# JLink-OB-072-Wiki.net
KiCad netlist of a schematic drawn in Altium Designer
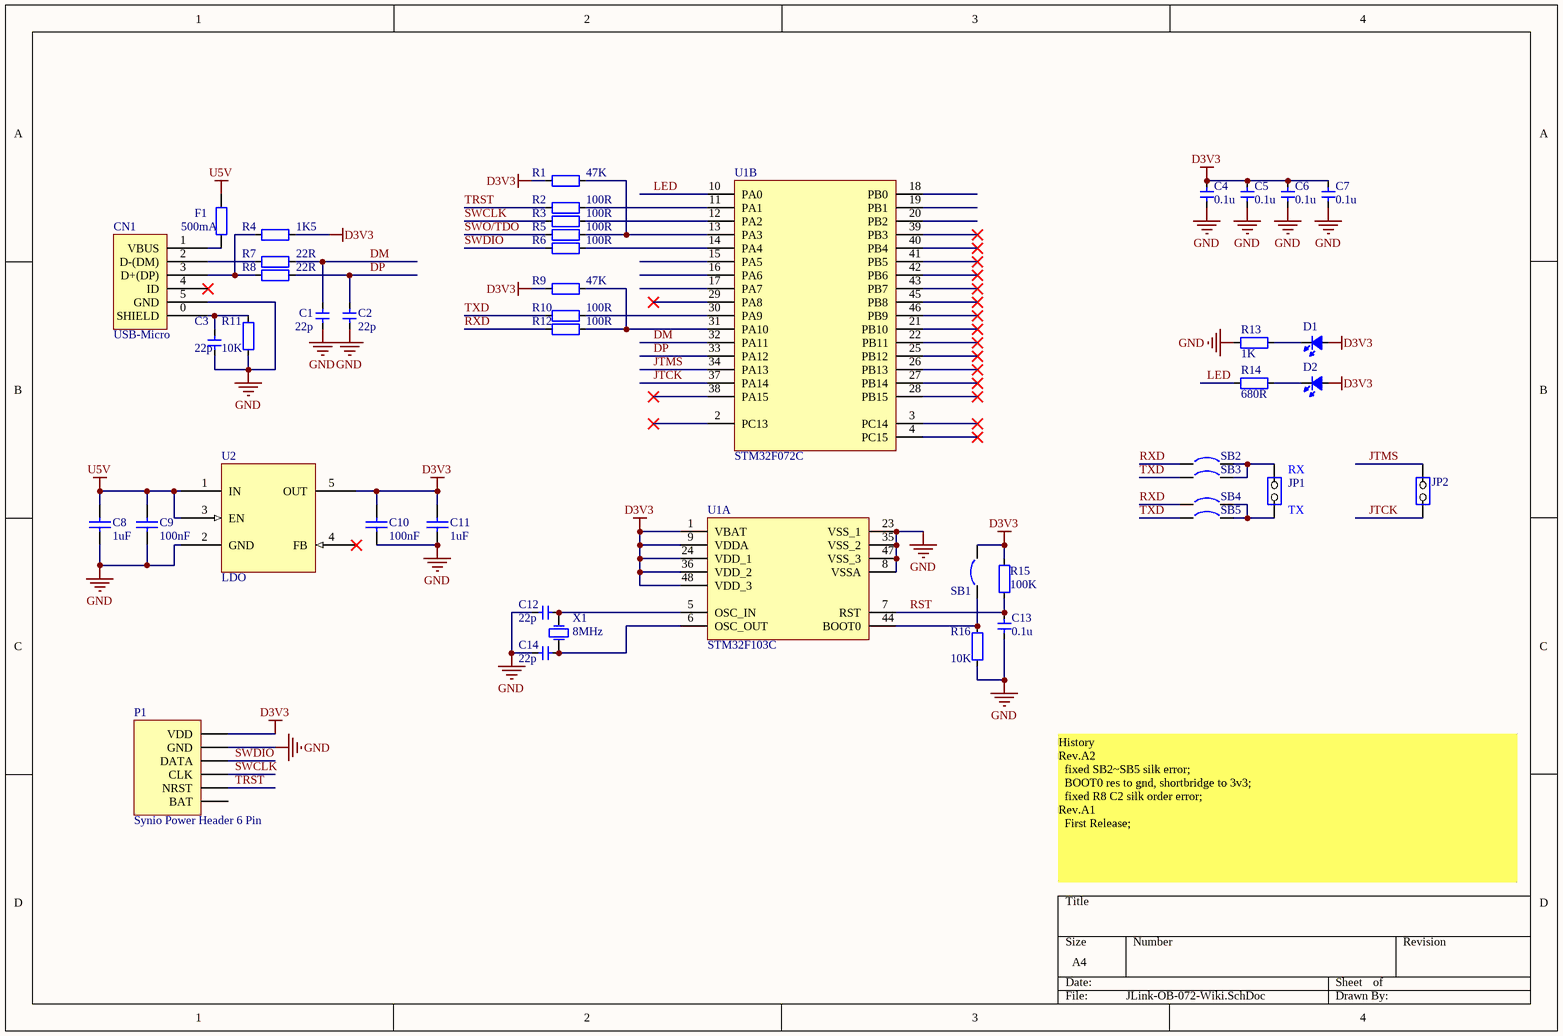
[diagram p0: JLink-OB-072-Wiki.SchDoc]

(export (version "E")
  (design (tool "Eeschema 10.0.6"))
  (components
    (comp (ref "C1")
      (value "22p")
      (footprint "0603C")
      (description "Capacitor")
      (fields (field (name "Comment") "Cap_0603"))
      (libsource (lib "altium-import") (part "root_1_Cap_0603_"))
    )
    (comp (ref "C2")
      (value "22p")
      (footprint "0603C")
      (description "Capacitor")
      (fields (field (name "Comment") "Cap_0603"))
      (libsource (lib "SCH_Passive") (part "Cap_0603"))
    )
    (comp (ref "C3")
      (value "22p")
      (footprint "0603C")
      (description "Capacitor")
      (fields (field (name "Comment") "Cap_0603"))
      (libsource (lib "SCH_Passive") (part "Cap_0603"))
    )
    (comp (ref "C4")
      (value "0.1u")
      (footprint "0603C")
      (description "Capacitor")
      (fields (field (name "Comment") "Cap_0603"))
      (libsource (lib "SCH_Passive") (part "Cap_0603"))
    )
    (comp (ref "C5")
      (value "0.1u")
      (footprint "0603C")
      (description "Capacitor")
      (fields (field (name "Comment") "Cap_0603"))
      (libsource (lib "SCH_Passive") (part "Cap_0603"))
    )
    (comp (ref "C6")
      (value "0.1u")
      (footprint "0603C")
      (description "Capacitor")
      (fields (field (name "Comment") "Cap_0603"))
      (libsource (lib "SCH_Passive") (part "Cap_0603"))
    )
    (comp (ref "C7")
      (value "0.1u")
      (footprint "0603C")
      (description "Capacitor")
      (fields (field (name "Comment") "Cap_0603"))
      (libsource (lib "SCH_Passive") (part "Cap_0603"))
    )
    (comp (ref "C8")
      (value "1uF")
      (footprint "0603C")
      (description "Capacitor 0402 / 0603 / 0805")
      (libsource (lib "MCD_TOOLS") (part "Capacitor_ST"))
    )
    (comp (ref "C9")
      (value "100nF")
      (footprint "0603C")
      (description "Capacitor 0402 / 0603 / 0805")
      (libsource (lib "MCD_TOOLS") (part "Capacitor_ST"))
    )
    (comp (ref "C10")
      (value "100nF")
      (footprint "0603C")
      (description "Capacitor 0402 / 0603 / 0805")
      (libsource (lib "MCD_TOOLS") (part "Capacitor_ST"))
    )
    (comp (ref "C11")
      (value "1uF")
      (footprint "0603C")
      (description "Capacitor 0402 / 0603 / 0805")
      (libsource (lib "MCD_TOOLS") (part "Capacitor_ST"))
    )
    (comp (ref "C12")
      (value "22p")
      (footprint "0603C")
      (description "Capacitor")
      (fields (field (name "Comment") "Cap_0603"))
      (libsource (lib "SCH_Passive") (part "Cap_0603"))
    )
    (comp (ref "C13")
      (value "0.1u")
      (footprint "0603C")
      (description "Capacitor")
      (fields (field (name "Comment") "Cap_0603"))
      (libsource (lib "SCH_Passive") (part "Cap_0603"))
    )
    (comp (ref "C14")
      (value "22p")
      (footprint "0603C")
      (description "Capacitor")
      (fields (field (name "Comment") "Cap_0603"))
      (libsource (lib "SCH_Passive") (part "Cap_0603"))
    )
    (comp (ref "CN1")
      (value "USB-Micro")
      (footprint "USB_MICRO_5S_B-2")
      (libsource (lib "USB") (part "USB-Micro"))
    )
    (comp (ref "D1")
      (value "LED_0603")
      (footprint "LED-0603")
      (description "LED")
      (libsource (lib "SCH_Active") (part "LED_0603"))
    )
    (comp (ref "D2")
      (value "LED_0603")
      (footprint "LED-0603")
      (description "LED")
      (libsource (lib "SCH_Active") (part "LED_0603"))
    )
    (comp (ref "F1")
      (value "500mA")
      (footprint "0805M")
      (description "Resistor")
      (fields (field (name "PUBLISHER") "Altium Limited"))
      (libsource (lib "Misc") (part "Res"))
    )
    (comp (ref "JP1") (value "JP2") (footprint "HDR1X2/2.54mm") (libsource (lib "Connector") (part "JP2")))
    (comp (ref "JP2") (value "JP2") (footprint "HDR1X2/2.54mm") (libsource (lib "Connector") (part "JP2")))
    (comp (ref "P1")
      (value "Synio Power Header 6 Pin")
      (footprint "HDR1X6/2.54MM")
      (libsource (lib "Connector") (part "Synio Power Header 6 Pin"))
    )
    (comp (ref "R1")
      (value "47K")
      (footprint "0603R")
      (description "Resistor")
      (fields (field (name "Comment") "Res_0603"))
      (libsource (lib "") (part "Res_0603_1"))
    )
    (comp (ref "R2")
      (value "100R")
      (footprint "0603R")
      (description "Resistor")
      (fields (field (name "Comment") "Res_0603"))
      (libsource (lib "altium-import") (part "root_0_Res_0603_"))
    )
    (comp (ref "R3")
      (value "100R")
      (footprint "0603R")
      (description "Resistor")
      (fields (field (name "Comment") "Res_0603"))
      (libsource (lib "SCH_Passive") (part "Res_0603"))
    )
    (comp (ref "R4")
      (value "1K5")
      (footprint "0603R")
      (description "Resistor")
      (fields (field (name "Comment") "Res_0603"))
      (libsource (lib "SCH_Passive") (part "Res_0603"))
    )
    (comp (ref "R5")
      (value "100R")
      (footprint "0603R")
      (description "Resistor")
      (fields (field (name "Comment") "Res_0603"))
      (libsource (lib "SCH_Passive") (part "Res_0603"))
    )
    (comp (ref "R6")
      (value "100R")
      (footprint "0603R")
      (description "Resistor")
      (fields (field (name "Comment") "Res_0603"))
      (libsource (lib "SCH_Passive") (part "Res_0603"))
    )
    (comp (ref "R7")
      (value "22R")
      (footprint "0603R")
      (description "Resistor")
      (fields (field (name "Comment") "Res_0603"))
      (libsource (lib "SCH_Passive") (part "Res_0603"))
    )
    (comp (ref "R8")
      (value "22R")
      (footprint "0603R")
      (description "Resistor")
      (fields (field (name "Comment") "Res_0603"))
      (libsource (lib "SCH_Passive") (part "Res_0603"))
    )
    (comp (ref "R9")
      (value "47K")
      (footprint "0603R")
      (description "Resistor")
      (fields (field (name "Comment") "Res_0603"))
      (libsource (lib "") (part "Res_0603_1"))
    )
    (comp (ref "R10")
      (value "100R")
      (footprint "0603R")
      (description "Resistor")
      (fields (field (name "Comment") "Res_0603"))
      (libsource (lib "SCH_Passive") (part "Res_0603"))
    )
    (comp (ref "R11")
      (value "10K")
      (footprint "0603R")
      (description "Resistor")
      (fields (field (name "Comment") "Res_0603"))
      (libsource (lib "") (part "Res_0603_3"))
    )
    (comp (ref "R12")
      (value "100R")
      (footprint "0603R")
      (description "Resistor")
      (fields (field (name "Comment") "Res_0603"))
      (libsource (lib "SCH_Passive") (part "Res_0603"))
    )
    (comp (ref "R13")
      (value "1K")
      (footprint "0603R")
      (description "Resistor")
      (fields (field (name "Comment") "Res_0603"))
      (libsource (lib "SCH_Passive") (part "Res_0603"))
    )
    (comp (ref "R14")
      (value "680R")
      (footprint "0603R")
      (description "Resistor")
      (fields (field (name "Comment") "Res_0603"))
      (libsource (lib "SCH_Passive") (part "Res_0603"))
    )
    (comp (ref "R15")
      (value "100K")
      (footprint "0603R")
      (description "Resistor")
      (fields (field (name "Comment") "Res_0603"))
      (libsource (lib "") (part "Res_0603_3"))
    )
    (comp (ref "R16")
      (value "10K")
      (footprint "0603R")
      (description "Resistor")
      (fields (field (name "Comment") "Res_0603"))
      (libsource (lib "") (part "Res_0603_2"))
    )
    (comp (ref "SB1")
      (value "Circuit Breaker")
      (footprint "JP2_SMD")
      (fields (field (name "PUBLISHER") "Altium Limited"))
      (libsource (lib "Misc") (part "Circuit Breaker"))
    )
    (comp (ref "SB2")
      (value "Circuit Breaker")
      (footprint "JP2_SMD")
      (fields (field (name "PUBLISHER") "Altium Limited"))
      (libsource (lib "Misc") (part "Circuit Breaker"))
    )
    (comp (ref "SB3")
      (value "Circuit Breaker")
      (footprint "JP2_SMD")
      (fields (field (name "PUBLISHER") "Altium Limited"))
      (libsource (lib "Misc") (part "Circuit Breaker"))
    )
    (comp (ref "SB4")
      (value "Circuit Breaker")
      (footprint "JP2_SMD")
      (fields (field (name "PUBLISHER") "Altium Limited"))
      (libsource (lib "Misc") (part "Circuit Breaker"))
    )
    (comp (ref "SB5")
      (value "Circuit Breaker")
      (footprint "JP2_SMD")
      (fields (field (name "PUBLISHER") "Altium Limited"))
      (libsource (lib "Misc") (part "Circuit Breaker"))
    )
    (comp (ref "U1")
      (value "STM32F103C")
      (footprint "LQFP48_N")
      (description "MCU")
      (libsource (lib "SCH_IC") (part "STM32F103C"))
    )
    (comp (ref "U2")
      (value "LDO")
      (footprint "SOT23-5")
      (description "General LDO SOT23-5")
      (libsource (lib "Power") (part "LDO-SOT23-5"))
    )
    (comp (ref "X1")
      (value "8MHz")
      (footprint "XTAL")
      (description "Crystal Oscillator")
      (fields (field (name "Comment") "XTAL_5032_2P"))
      (libsource (lib "SCH_Oscillator") (part "XTAL_5032_2P"))
    )
  )
  (nets
    (net (code "1") (name "/DM") (class "Default")
      (node (ref "C1") (pin "2") (pinfunction "2_2") (pintype "passive"))
      (node (ref "R7") (pin "2") (pinfunction "2_2") (pintype "passive"))
      (node (ref "U1") (pin "32") (pinfunction "PA11_32") (pintype "passive"))
    )
    (net (code "2") (name "/DP") (class "Default")
      (node (ref "C2") (pin "2") (pinfunction "2_2") (pintype "passive"))
      (node (ref "R8") (pin "2") (pinfunction "2_2") (pintype "passive"))
      (node (ref "U1") (pin "33") (pinfunction "PA12_33") (pintype "passive"))
    )
    (net (code "3") (name "/JTCK") (class "Default")
      (node (ref "JP2") (pin "1") (pinfunction "COMMON_1") (pintype "passive"))
      (node (ref "U1") (pin "37") (pinfunction "PA14_37") (pintype "passive"))
    )
    (net (code "4") (name "/JTMS") (class "Default")
      (node (ref "JP2") (pin "2") (pinfunction "NO_2") (pintype "passive"))
      (node (ref "U1") (pin "34") (pinfunction "PA13_34") (pintype "passive"))
    )
    (net (code "5") (name "/LED") (class "Default")
      (node (ref "R14") (pin "1") (pinfunction "1_1") (pintype "passive"))
      (node (ref "U1") (pin "10") (pinfunction "PA0_10") (pintype "passive"))
    )
    (net (code "6") (name "/RST") (class "Default")
      (node (ref "C13") (pin "1") (pinfunction "1_1") (pintype "passive"))
      (node (ref "R15") (pin "1") (pinfunction "1_1") (pintype "passive"))
      (node (ref "U1") (pin "7") (pinfunction "RST_7") (pintype "passive"))
    )
    (net (code "7") (name "/RXD") (class "Default")
      (node (ref "R12") (pin "1") (pinfunction "1_1") (pintype "passive"))
      (node (ref "SB2") (pin "1") (pinfunction "1_1") (pintype "passive"))
      (node (ref "SB4") (pin "1") (pinfunction "1_1") (pintype "passive"))
    )
    (net (code "8") (name "/SWCLK") (class "Default")
      (node (ref "P1") (pin "4") (pinfunction "CLK_4") (pintype "passive"))
      (node (ref "R3") (pin "1") (pinfunction "1_1") (pintype "passive"))
    )
    (net (code "9") (name "/SWDIO") (class "Default")
      (node (ref "P1") (pin "3") (pinfunction "DATA_3") (pintype "passive"))
      (node (ref "R6") (pin "1") (pinfunction "1_1") (pintype "passive"))
    )
    (net (code "10") (name "/SWO{slash}TDO") (class "Default")
      (node (ref "R5") (pin "1") (pinfunction "1_1") (pintype "passive"))
    )
    (net (code "11") (name "/TRST") (class "Default")
      (node (ref "P1") (pin "5") (pinfunction "NRST_5") (pintype "passive"))
      (node (ref "R2") (pin "1") (pinfunction "1_1") (pintype "passive"))
    )
    (net (code "12") (name "/TXD") (class "Default")
      (node (ref "R10") (pin "1") (pinfunction "1_1") (pintype "passive"))
      (node (ref "SB3") (pin "1") (pinfunction "1_1") (pintype "passive"))
      (node (ref "SB5") (pin "1") (pinfunction "1_1") (pintype "passive"))
    )
    (net (code "13") (name "D3V3") (class "Default")
      (node (ref "C10") (pin "2") (pinfunction "2_2") (pintype "passive"))
      (node (ref "C11") (pin "1") (pinfunction "1_1") (pintype "passive"))
      (node (ref "C4") (pin "1") (pinfunction "1_1") (pintype "passive"))
      (node (ref "C5") (pin "1") (pinfunction "1_1") (pintype "passive"))
      (node (ref "C6") (pin "1") (pinfunction "1_1") (pintype "passive"))
      (node (ref "C7") (pin "1") (pinfunction "1_1") (pintype "passive"))
      (node (ref "D1") (pin "1") (pinfunction "A_1") (pintype "passive"))
      (node (ref "D2") (pin "1") (pinfunction "A_1") (pintype "passive"))
      (node (ref "P1") (pin "1") (pinfunction "VDD_1") (pintype "passive"))
      (node (ref "R1") (pin "2") (pinfunction "2_2") (pintype "passive"))
      (node (ref "R15") (pin "2") (pinfunction "2_2") (pintype "passive"))
      (node (ref "R4") (pin "2") (pinfunction "2_2") (pintype "passive"))
      (node (ref "R9") (pin "2") (pinfunction "2_2") (pintype "passive"))
      (node (ref "SB1") (pin "2") (pinfunction "2_2") (pintype "passive"))
      (node (ref "U1") (pin "1") (pinfunction "VBAT_1") (pintype "passive"))
      (node (ref "U1") (pin "24") (pinfunction "VDD_1_24") (pintype "passive"))
      (node (ref "U1") (pin "36") (pinfunction "VDD_2_36") (pintype "passive"))
      (node (ref "U1") (pin "48") (pinfunction "VDD_3_48") (pintype "passive"))
      (node (ref "U1") (pin "9") (pinfunction "VDDA_9") (pintype "passive"))
      (node (ref "U2") (pin "5") (pinfunction "OUT_5") (pintype "power_in"))
    )
    (net (code "14") (name "GND") (class "Default")
      (node (ref "C1") (pin "1") (pinfunction "1_1") (pintype "passive"))
      (node (ref "C10") (pin "1") (pinfunction "1_1") (pintype "passive"))
      (node (ref "C11") (pin "2") (pinfunction "2_2") (pintype "passive"))
      (node (ref "C12") (pin "2") (pinfunction "2_2") (pintype "passive"))
      (node (ref "C13") (pin "2") (pinfunction "2_2") (pintype "passive"))
      (node (ref "C14") (pin "2") (pinfunction "2_2") (pintype "passive"))
      (node (ref "C2") (pin "1") (pinfunction "1_1") (pintype "passive"))
      (node (ref "C3") (pin "1") (pinfunction "1_1") (pintype "passive"))
      (node (ref "C4") (pin "2") (pinfunction "2_2") (pintype "passive"))
      (node (ref "C5") (pin "2") (pinfunction "2_2") (pintype "passive"))
      (node (ref "C6") (pin "2") (pinfunction "2_2") (pintype "passive"))
      (node (ref "C7") (pin "2") (pinfunction "2_2") (pintype "passive"))
      (node (ref "C8") (pin "1") (pinfunction "1_1") (pintype "passive"))
      (node (ref "C9") (pin "1") (pinfunction "1_1") (pintype "passive"))
      (node (ref "CN1") (pin "5") (pinfunction "GND_5") (pintype "passive"))
      (node (ref "P1") (pin "2") (pinfunction "GND_2") (pintype "passive"))
      (node (ref "R11") (pin "1") (pinfunction "1_1") (pintype "passive"))
      (node (ref "R13") (pin "1") (pinfunction "1_1") (pintype "passive"))
      (node (ref "R16") (pin "2") (pinfunction "2_2") (pintype "passive"))
      (node (ref "U1") (pin "23") (pinfunction "VSS_1_23") (pintype "passive"))
      (node (ref "U1") (pin "35") (pinfunction "VSS_2_35") (pintype "passive"))
      (node (ref "U1") (pin "47") (pinfunction "VSS_3_47") (pintype "passive"))
      (node (ref "U1") (pin "8") (pinfunction "VSSA_8") (pintype "passive"))
      (node (ref "U2") (pin "2") (pinfunction "GND_2") (pintype "power_in"))
    )
    (net (code "15") (name "Net-(CN1-D+(DP))") (class "Default")
      (node (ref "CN1") (pin "3") (pinfunction "D+(DP)_3") (pintype "passive"))
      (node (ref "R4") (pin "1") (pinfunction "1_1") (pintype "passive"))
      (node (ref "R8") (pin "1") (pinfunction "1_1") (pintype "passive"))
    )
    (net (code "16") (name "Net-(CN1-D-(DM))") (class "Default")
      (node (ref "CN1") (pin "2") (pinfunction "D-(DM)_2") (pintype "passive"))
      (node (ref "R7") (pin "1") (pinfunction "1_1") (pintype "passive"))
    )
    (net (code "17") (name "Net-(CN1-SHIELD)") (class "Default")
      (node (ref "C3") (pin "2") (pinfunction "2_2") (pintype "passive"))
      (node (ref "CN1") (pin "0") (pinfunction "SHIELD_0") (pintype "passive"))
      (node (ref "R11") (pin "2") (pinfunction "2_2") (pintype "passive"))
    )
    (net (code "18") (name "Net-(CN1-VBUS)") (class "Default")
      (node (ref "CN1") (pin "1") (pinfunction "VBUS_1") (pintype "passive"))
      (node (ref "F1") (pin "1") (pinfunction "1_1") (pintype "passive"))
    )
    (net (code "19") (name "Net-(D1-K)") (class "Default")
      (node (ref "D1") (pin "2") (pinfunction "K_2") (pintype "passive"))
      (node (ref "R13") (pin "2") (pinfunction "2_2") (pintype "passive"))
    )
    (net (code "20") (name "Net-(D2-K)") (class "Default")
      (node (ref "D2") (pin "2") (pinfunction "K_2") (pintype "passive"))
      (node (ref "R14") (pin "2") (pinfunction "2_2") (pintype "passive"))
    )
    (net (code "21") (name "Net-(JP1-COMMON)") (class "Default")
      (node (ref "JP1") (pin "1") (pinfunction "COMMON_1") (pintype "passive"))
      (node (ref "SB4") (pin "2") (pinfunction "2_2") (pintype "passive"))
      (node (ref "SB5") (pin "2") (pinfunction "2_2") (pintype "passive"))
    )
    (net (code "22") (name "Net-(JP1-NO)") (class "Default")
      (node (ref "JP1") (pin "2") (pinfunction "NO_2") (pintype "passive"))
      (node (ref "SB2") (pin "2") (pinfunction "2_2") (pintype "passive"))
      (node (ref "SB3") (pin "2") (pinfunction "2_2") (pintype "passive"))
    )
    (net (code "23") (name "Net-(U1A-BOOT0)") (class "Default")
      (node (ref "R16") (pin "1") (pinfunction "1_1") (pintype "passive"))
      (node (ref "SB1") (pin "1") (pinfunction "1_1") (pintype "passive"))
      (node (ref "U1") (pin "44") (pinfunction "BOOT0_44") (pintype "passive"))
    )
    (net (code "24") (name "Net-(U1A-OSC_IN)") (class "Default")
      (node (ref "C12") (pin "1") (pinfunction "1_1") (pintype "passive"))
      (node (ref "U1") (pin "5") (pinfunction "OSC_IN_5") (pintype "passive"))
      (node (ref "X1") (pin "2") (pinfunction "OSC2_2") (pintype "passive"))
    )
    (net (code "25") (name "Net-(U1A-OSC_OUT)") (class "Default")
      (node (ref "C14") (pin "1") (pinfunction "1_1") (pintype "passive"))
      (node (ref "U1") (pin "6") (pinfunction "OSC_OUT_6") (pintype "passive"))
      (node (ref "X1") (pin "1") (pinfunction "OSC1_1") (pintype "passive"))
    )
    (net (code "26") (name "Net-(U1B-PA1)") (class "Default")
      (node (ref "R2") (pin "2") (pinfunction "2_2") (pintype "passive"))
      (node (ref "U1") (pin "11") (pinfunction "PA1_11") (pintype "passive"))
    )
    (net (code "27") (name "Net-(U1B-PA2)") (class "Default")
      (node (ref "R3") (pin "2") (pinfunction "2_2") (pintype "passive"))
      (node (ref "U1") (pin "12") (pinfunction "PA2_12") (pintype "passive"))
    )
    (net (code "28") (name "Net-(U1B-PA3)") (class "Default")
      (node (ref "R1") (pin "1") (pinfunction "1_1") (pintype "passive"))
      (node (ref "R5") (pin "2") (pinfunction "2_2") (pintype "passive"))
      (node (ref "U1") (pin "13") (pinfunction "PA3_13") (pintype "passive"))
    )
    (net (code "29") (name "Net-(U1B-PA4)") (class "Default")
      (node (ref "R6") (pin "2") (pinfunction "2_2") (pintype "passive"))
      (node (ref "U1") (pin "14") (pinfunction "PA4_14") (pintype "passive"))
    )
    (net (code "30") (name "Net-(U1B-PA9)") (class "Default")
      (node (ref "R10") (pin "2") (pinfunction "2_2") (pintype "passive"))
      (node (ref "U1") (pin "30") (pinfunction "PA9_30") (pintype "passive"))
    )
    (net (code "31") (name "Net-(U1B-PA10)") (class "Default")
      (node (ref "R12") (pin "2") (pinfunction "2_2") (pintype "passive"))
      (node (ref "R9") (pin "1") (pinfunction "1_1") (pintype "passive"))
      (node (ref "U1") (pin "31") (pinfunction "PA10_31") (pintype "passive"))
    )
    (net (code "32") (name "U5V") (class "Default")
      (node (ref "C8") (pin "2") (pinfunction "2_2") (pintype "passive"))
      (node (ref "C9") (pin "2") (pinfunction "2_2") (pintype "passive"))
      (node (ref "F1") (pin "2") (pinfunction "2_2") (pintype "passive"))
      (node (ref "U2") (pin "1") (pinfunction "IN_1") (pintype "power_in"))
      (node (ref "U2") (pin "3") (pinfunction "EN_3") (pintype "input"))
    )
    (net (code "33") (name "unconnected-(CN1-ID-Pad4)") (class "Default")
      (node (ref "CN1") (pin "4") (pinfunction "ID_4") (pintype "passive+no_connect"))
    )
    (net (code "34") (name "unconnected-(P1-BAT-Pad6)") (class "Default")
      (node (ref "P1") (pin "6") (pinfunction "BAT_6") (pintype "passive"))
    )
    (net (code "35") (name "unconnected-(U1B-PA5-Pad15)") (class "Default")
      (node (ref "U1") (pin "15") (pinfunction "PA5_15") (pintype "passive"))
    )
    (net (code "36") (name "unconnected-(U1B-PA6-Pad16)") (class "Default")
      (node (ref "U1") (pin "16") (pinfunction "PA6_16") (pintype "passive"))
    )
    (net (code "37") (name "unconnected-(U1B-PA7-Pad17)") (class "Default")
      (node (ref "U1") (pin "17") (pinfunction "PA7_17") (pintype "passive"))
    )
    (net (code "38") (name "unconnected-(U1B-PA8-Pad29)") (class "Default")
      (node (ref "U1") (pin "29") (pinfunction "PA8_29") (pintype "passive+no_connect"))
    )
    (net (code "39") (name "unconnected-(U1B-PA15-Pad38)") (class "Default")
      (node (ref "U1") (pin "38") (pinfunction "PA15_38") (pintype "passive+no_connect"))
    )
    (net (code "40") (name "unconnected-(U1B-PB0-Pad18)") (class "Default")
      (node (ref "U1") (pin "18") (pinfunction "PB0_18") (pintype "passive"))
    )
    (net (code "41") (name "unconnected-(U1B-PB1-Pad19)") (class "Default")
      (node (ref "U1") (pin "19") (pinfunction "PB1_19") (pintype "passive"))
    )
    (net (code "42") (name "unconnected-(U1B-PB2-Pad20)") (class "Default")
      (node (ref "U1") (pin "20") (pinfunction "PB2_20") (pintype "passive"))
    )
    (net (code "43") (name "unconnected-(U1B-PB3-Pad39)") (class "Default")
      (node (ref "U1") (pin "39") (pinfunction "PB3_39") (pintype "passive+no_connect"))
    )
    (net (code "44") (name "unconnected-(U1B-PB4-Pad40)") (class "Default")
      (node (ref "U1") (pin "40") (pinfunction "PB4_40") (pintype "passive+no_connect"))
    )
    (net (code "45") (name "unconnected-(U1B-PB5-Pad41)") (class "Default")
      (node (ref "U1") (pin "41") (pinfunction "PB5_41") (pintype "passive+no_connect"))
    )
    (net (code "46") (name "unconnected-(U1B-PB6-Pad42)") (class "Default")
      (node (ref "U1") (pin "42") (pinfunction "PB6_42") (pintype "passive+no_connect"))
    )
    (net (code "47") (name "unconnected-(U1B-PB7-Pad43)") (class "Default")
      (node (ref "U1") (pin "43") (pinfunction "PB7_43") (pintype "passive+no_connect"))
    )
    (net (code "48") (name "unconnected-(U1B-PB8-Pad45)") (class "Default")
      (node (ref "U1") (pin "45") (pinfunction "PB8_45") (pintype "passive+no_connect"))
    )
    (net (code "49") (name "unconnected-(U1B-PB9-Pad46)") (class "Default")
      (node (ref "U1") (pin "46") (pinfunction "PB9_46") (pintype "passive+no_connect"))
    )
    (net (code "50") (name "unconnected-(U1B-PB10-Pad21)") (class "Default")
      (node (ref "U1") (pin "21") (pinfunction "PB10_21") (pintype "passive+no_connect"))
    )
    (net (code "51") (name "unconnected-(U1B-PB11-Pad22)") (class "Default")
      (node (ref "U1") (pin "22") (pinfunction "PB11_22") (pintype "passive+no_connect"))
    )
    (net (code "52") (name "unconnected-(U1B-PB12-Pad25)") (class "Default")
      (node (ref "U1") (pin "25") (pinfunction "PB12_25") (pintype "passive+no_connect"))
    )
    (net (code "53") (name "unconnected-(U1B-PB13-Pad26)") (class "Default")
      (node (ref "U1") (pin "26") (pinfunction "PB13_26") (pintype "passive+no_connect"))
    )
    (net (code "54") (name "unconnected-(U1B-PB14-Pad27)") (class "Default")
      (node (ref "U1") (pin "27") (pinfunction "PB14_27") (pintype "passive+no_connect"))
    )
    (net (code "55") (name "unconnected-(U1B-PB15-Pad28)") (class "Default")
      (node (ref "U1") (pin "28") (pinfunction "PB15_28") (pintype "passive+no_connect"))
    )
    (net (code "56") (name "unconnected-(U1B-PC13-Pad2)") (class "Default")
      (node (ref "U1") (pin "2") (pinfunction "PC13_2") (pintype "passive+no_connect"))
    )
    (net (code "57") (name "unconnected-(U1B-PC14-Pad3)") (class "Default")
      (node (ref "U1") (pin "3") (pinfunction "PC14_3") (pintype "passive+no_connect"))
    )
    (net (code "58") (name "unconnected-(U1B-PC15-Pad4)") (class "Default")
      (node (ref "U1") (pin "4") (pinfunction "PC15_4") (pintype "passive+no_connect"))
    )
    (net (code "59") (name "unconnected-(U2-FB-Pad4)") (class "Default")
      (node (ref "U2") (pin "4") (pinfunction "FB_4") (pintype "input+no_connect"))
    )
  )
)
